# ESP-32_Stepper_Hat_v6.net
KiCad netlist of a schematic drawn in EAGLE
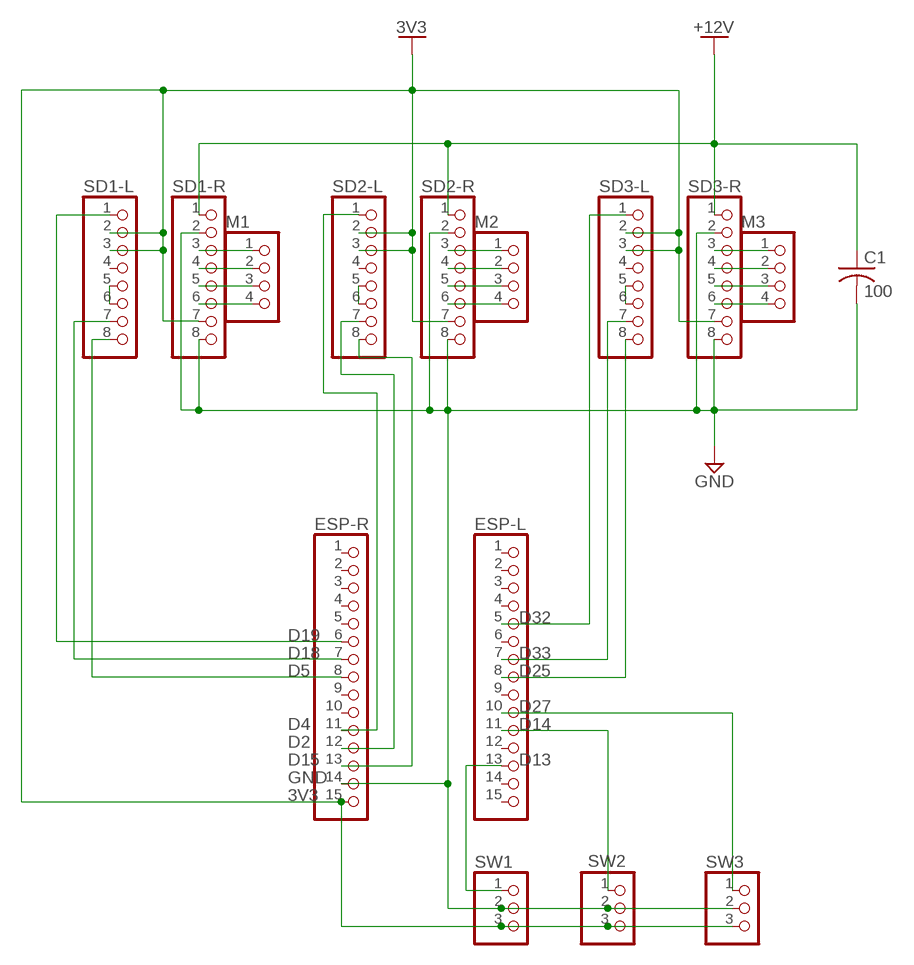
[diagram p0: schematic, sheet 1]

(export (version "E")
  (design (tool "Eeschema 10.0.6"))
  (components
    (comp (ref "C1")
      (value "100")
      (footprint "eagle-import:CAPRD550W60D1025H1250B")
      (libsource (lib "eagle-import") (part "C-USRADIAL-12.5MM-DIA_"))
    )
    (comp (ref "ESP-L")
      (value "PINHD-1X15")
      (footprint "eagle-import:1X15")
      (libsource (lib "eagle-import") (part "PINHD-1X15"))
    )
    (comp (ref "ESP-R")
      (value "PINHD-1X15")
      (footprint "eagle-import:1X15")
      (libsource (lib "eagle-import") (part "PINHD-1X15"))
    )
    (comp (ref "M1")
      (value "PINHD-1X4")
      (footprint "eagle-import:1X04")
      (libsource (lib "eagle-import") (part "PINHD-1X4"))
    )
    (comp (ref "M2")
      (value "PINHD-1X4")
      (footprint "eagle-import:1X04")
      (libsource (lib "eagle-import") (part "PINHD-1X4"))
    )
    (comp (ref "M3")
      (value "PINHD-1X4")
      (footprint "eagle-import:1X04")
      (libsource (lib "eagle-import") (part "PINHD-1X4"))
    )
    (comp (ref "SD1-L")
      (value "PINHD-1X8")
      (footprint "eagle-import:1X08")
      (libsource (lib "eagle-import") (part "PINHD-1X8"))
    )
    (comp (ref "SD1-R")
      (value "PINHD-1X8")
      (footprint "eagle-import:1X08")
      (libsource (lib "eagle-import") (part "PINHD-1X8"))
    )
    (comp (ref "SD2-L")
      (value "PINHD-1X8")
      (footprint "eagle-import:1X08")
      (libsource (lib "eagle-import") (part "PINHD-1X8"))
    )
    (comp (ref "SD2-R")
      (value "PINHD-1X8")
      (footprint "eagle-import:1X08")
      (libsource (lib "eagle-import") (part "PINHD-1X8"))
    )
    (comp (ref "SD3-L")
      (value "PINHD-1X8")
      (footprint "eagle-import:1X08")
      (libsource (lib "eagle-import") (part "PINHD-1X8"))
    )
    (comp (ref "SD3-R")
      (value "PINHD-1X8")
      (footprint "eagle-import:1X08")
      (libsource (lib "eagle-import") (part "PINHD-1X8"))
    )
    (comp (ref "SW1")
      (value "PINHD-1X3")
      (footprint "eagle-import:1X03")
      (libsource (lib "eagle-import") (part "PINHD-1X3"))
    )
    (comp (ref "SW2")
      (value "PINHD-1X3")
      (footprint "eagle-import:1X03")
      (libsource (lib "eagle-import") (part "PINHD-1X3"))
    )
    (comp (ref "SW3")
      (value "PINHD-1X3")
      (footprint "eagle-import:1X03")
      (libsource (lib "eagle-import") (part "PINHD-1X3"))
    )
  )
  (nets
    (net (code "1") (name "+12V") (class "Default")
      (node (ref "C1") (pin "1") (pinfunction "1_1") (pintype "passive"))
      (node (ref "SD1-R") (pin "1") (pinfunction "1_1") (pintype "passive"))
      (node (ref "SD2-R") (pin "1") (pinfunction "1_1") (pintype "passive"))
      (node (ref "SD3-R") (pin "1") (pinfunction "1_1") (pintype "passive"))
    )
    (net (code "2") (name "/D2") (class "Default")
      (node (ref "ESP-R") (pin "12") (pinfunction "12_12") (pintype "passive"))
      (node (ref "SD2-L") (pin "7") (pinfunction "7_7") (pintype "passive"))
    )
    (net (code "3") (name "/D4") (class "Default")
      (node (ref "ESP-R") (pin "11") (pinfunction "11_11") (pintype "passive"))
      (node (ref "SD2-L") (pin "1") (pinfunction "1_1") (pintype "passive"))
    )
    (net (code "4") (name "/D5") (class "Default")
      (node (ref "ESP-R") (pin "8") (pinfunction "8_8") (pintype "passive"))
      (node (ref "SD1-L") (pin "8") (pinfunction "8_8") (pintype "passive"))
    )
    (net (code "5") (name "/D13") (class "Default")
      (node (ref "ESP-L") (pin "13") (pinfunction "13_13") (pintype "passive"))
      (node (ref "SW1") (pin "1") (pinfunction "1_1") (pintype "passive"))
    )
    (net (code "6") (name "/D14") (class "Default")
      (node (ref "ESP-L") (pin "11") (pinfunction "11_11") (pintype "passive"))
      (node (ref "SW2") (pin "1") (pinfunction "1_1") (pintype "passive"))
    )
    (net (code "7") (name "/D15") (class "Default")
      (node (ref "ESP-R") (pin "13") (pinfunction "13_13") (pintype "passive"))
      (node (ref "SD2-L") (pin "8") (pinfunction "8_8") (pintype "passive"))
    )
    (net (code "8") (name "/D18") (class "Default")
      (node (ref "ESP-R") (pin "7") (pinfunction "7_7") (pintype "passive"))
      (node (ref "SD1-L") (pin "7") (pinfunction "7_7") (pintype "passive"))
    )
    (net (code "9") (name "/D19") (class "Default")
      (node (ref "ESP-R") (pin "6") (pinfunction "6_6") (pintype "passive"))
      (node (ref "SD1-L") (pin "1") (pinfunction "1_1") (pintype "passive"))
    )
    (net (code "10") (name "/D25") (class "Default")
      (node (ref "ESP-L") (pin "8") (pinfunction "8_8") (pintype "passive"))
      (node (ref "SD3-L") (pin "8") (pinfunction "8_8") (pintype "passive"))
    )
    (net (code "11") (name "/D27") (class "Default")
      (node (ref "ESP-L") (pin "10") (pinfunction "10_10") (pintype "passive"))
      (node (ref "SW3") (pin "1") (pinfunction "1_1") (pintype "passive"))
    )
    (net (code "12") (name "/D32") (class "Default")
      (node (ref "ESP-L") (pin "5") (pinfunction "5_5") (pintype "passive"))
      (node (ref "SD3-L") (pin "1") (pinfunction "1_1") (pintype "passive"))
    )
    (net (code "13") (name "/D33") (class "Default")
      (node (ref "ESP-L") (pin "7") (pinfunction "7_7") (pintype "passive"))
      (node (ref "SD3-L") (pin "7") (pinfunction "7_7") (pintype "passive"))
    )
    (net (code "14") (name "3V3") (class "Default")
      (node (ref "ESP-R") (pin "15") (pinfunction "15_15") (pintype "passive"))
      (node (ref "SD1-L") (pin "2") (pinfunction "2_2") (pintype "passive"))
      (node (ref "SD1-L") (pin "3") (pinfunction "3_3") (pintype "passive"))
      (node (ref "SD1-R") (pin "7") (pinfunction "7_7") (pintype "passive"))
      (node (ref "SD2-L") (pin "2") (pinfunction "2_2") (pintype "passive"))
      (node (ref "SD2-L") (pin "3") (pinfunction "3_3") (pintype "passive"))
      (node (ref "SD2-R") (pin "7") (pinfunction "7_7") (pintype "passive"))
      (node (ref "SD3-L") (pin "2") (pinfunction "2_2") (pintype "passive"))
      (node (ref "SD3-L") (pin "3") (pinfunction "3_3") (pintype "passive"))
      (node (ref "SD3-R") (pin "7") (pinfunction "7_7") (pintype "passive"))
      (node (ref "SW1") (pin "3") (pinfunction "3_3") (pintype "passive"))
      (node (ref "SW2") (pin "3") (pinfunction "3_3") (pintype "passive"))
      (node (ref "SW3") (pin "3") (pinfunction "3_3") (pintype "passive"))
    )
    (net (code "15") (name "GND") (class "Default")
      (node (ref "C1") (pin "2") (pinfunction "2_2") (pintype "passive"))
      (node (ref "ESP-R") (pin "14") (pinfunction "14_14") (pintype "passive"))
      (node (ref "SD1-R") (pin "2") (pinfunction "2_2") (pintype "passive"))
      (node (ref "SD1-R") (pin "8") (pinfunction "8_8") (pintype "passive"))
      (node (ref "SD2-R") (pin "2") (pinfunction "2_2") (pintype "passive"))
      (node (ref "SD2-R") (pin "8") (pinfunction "8_8") (pintype "passive"))
      (node (ref "SD3-R") (pin "2") (pinfunction "2_2") (pintype "passive"))
      (node (ref "SD3-R") (pin "8") (pinfunction "8_8") (pintype "passive"))
      (node (ref "SW1") (pin "2") (pinfunction "2_2") (pintype "passive"))
      (node (ref "SW2") (pin "2") (pinfunction "2_2") (pintype "passive"))
      (node (ref "SW3") (pin "2") (pinfunction "2_2") (pintype "passive"))
    )
    (net (code "16") (name "Net-(M1-Pad1)") (class "Default")
      (node (ref "M1") (pin "1") (pinfunction "1_1") (pintype "passive"))
      (node (ref "SD1-R") (pin "3") (pinfunction "3_3") (pintype "passive"))
    )
    (net (code "17") (name "Net-(M1-Pad2)") (class "Default")
      (node (ref "M1") (pin "2") (pinfunction "2_2") (pintype "passive"))
      (node (ref "SD1-R") (pin "4") (pinfunction "4_4") (pintype "passive"))
    )
    (net (code "18") (name "Net-(M1-Pad3)") (class "Default")
      (node (ref "M1") (pin "3") (pinfunction "3_3") (pintype "passive"))
      (node (ref "SD1-R") (pin "5") (pinfunction "5_5") (pintype "passive"))
    )
    (net (code "19") (name "Net-(M1-Pad4)") (class "Default")
      (node (ref "M1") (pin "4") (pinfunction "4_4") (pintype "passive"))
      (node (ref "SD1-R") (pin "6") (pinfunction "6_6") (pintype "passive"))
    )
    (net (code "20") (name "Net-(M2-Pad1)") (class "Default")
      (node (ref "M2") (pin "1") (pinfunction "1_1") (pintype "passive"))
      (node (ref "SD2-R") (pin "3") (pinfunction "3_3") (pintype "passive"))
    )
    (net (code "21") (name "Net-(M2-Pad2)") (class "Default")
      (node (ref "M2") (pin "2") (pinfunction "2_2") (pintype "passive"))
      (node (ref "SD2-R") (pin "4") (pinfunction "4_4") (pintype "passive"))
    )
    (net (code "22") (name "Net-(M2-Pad3)") (class "Default")
      (node (ref "M2") (pin "3") (pinfunction "3_3") (pintype "passive"))
      (node (ref "SD2-R") (pin "5") (pinfunction "5_5") (pintype "passive"))
    )
    (net (code "23") (name "Net-(M2-Pad4)") (class "Default")
      (node (ref "M2") (pin "4") (pinfunction "4_4") (pintype "passive"))
      (node (ref "SD2-R") (pin "6") (pinfunction "6_6") (pintype "passive"))
    )
    (net (code "24") (name "Net-(M3-Pad1)") (class "Default")
      (node (ref "M3") (pin "1") (pinfunction "1_1") (pintype "passive"))
      (node (ref "SD3-R") (pin "3") (pinfunction "3_3") (pintype "passive"))
    )
    (net (code "25") (name "Net-(M3-Pad2)") (class "Default")
      (node (ref "M3") (pin "2") (pinfunction "2_2") (pintype "passive"))
      (node (ref "SD3-R") (pin "4") (pinfunction "4_4") (pintype "passive"))
    )
    (net (code "26") (name "Net-(M3-Pad3)") (class "Default")
      (node (ref "M3") (pin "3") (pinfunction "3_3") (pintype "passive"))
      (node (ref "SD3-R") (pin "5") (pinfunction "5_5") (pintype "passive"))
    )
    (net (code "27") (name "Net-(M3-Pad4)") (class "Default")
      (node (ref "M3") (pin "4") (pinfunction "4_4") (pintype "passive"))
      (node (ref "SD3-R") (pin "6") (pinfunction "6_6") (pintype "passive"))
    )
    (net (code "28") (name "Net-(SD1-L-Pad5)") (class "Default")
      (node (ref "SD1-L") (pin "5") (pinfunction "5_5") (pintype "passive"))
      (node (ref "SD1-L") (pin "6") (pinfunction "6_6") (pintype "passive"))
    )
    (net (code "29") (name "Net-(SD2-L-Pad5)") (class "Default")
      (node (ref "SD2-L") (pin "5") (pinfunction "5_5") (pintype "passive"))
      (node (ref "SD2-L") (pin "6") (pinfunction "6_6") (pintype "passive"))
    )
    (net (code "30") (name "Net-(SD3-L-Pad5)") (class "Default")
      (node (ref "SD3-L") (pin "5") (pinfunction "5_5") (pintype "passive"))
      (node (ref "SD3-L") (pin "6") (pinfunction "6_6") (pintype "passive"))
    )
    (net (code "31") (name "unconnected-(ESP-L-Pad1)") (class "Default")
      (node (ref "ESP-L") (pin "1") (pinfunction "1_1") (pintype "passive"))
    )
    (net (code "32") (name "unconnected-(ESP-L-Pad2)") (class "Default")
      (node (ref "ESP-L") (pin "2") (pinfunction "2_2") (pintype "passive"))
    )
    (net (code "33") (name "unconnected-(ESP-L-Pad3)") (class "Default")
      (node (ref "ESP-L") (pin "3") (pinfunction "3_3") (pintype "passive"))
    )
    (net (code "34") (name "unconnected-(ESP-L-Pad4)") (class "Default")
      (node (ref "ESP-L") (pin "4") (pinfunction "4_4") (pintype "passive"))
    )
    (net (code "35") (name "unconnected-(ESP-L-Pad6)") (class "Default")
      (node (ref "ESP-L") (pin "6") (pinfunction "6_6") (pintype "passive"))
    )
    (net (code "36") (name "unconnected-(ESP-L-Pad9)") (class "Default")
      (node (ref "ESP-L") (pin "9") (pinfunction "9_9") (pintype "passive"))
    )
    (net (code "37") (name "unconnected-(ESP-L-Pad12)") (class "Default")
      (node (ref "ESP-L") (pin "12") (pinfunction "12_12") (pintype "passive"))
    )
    (net (code "38") (name "unconnected-(ESP-L-Pad14)") (class "Default")
      (node (ref "ESP-L") (pin "14") (pinfunction "14_14") (pintype "passive"))
    )
    (net (code "39") (name "unconnected-(ESP-L-Pad15)") (class "Default")
      (node (ref "ESP-L") (pin "15") (pinfunction "15_15") (pintype "passive"))
    )
    (net (code "40") (name "unconnected-(ESP-R-Pad1)") (class "Default")
      (node (ref "ESP-R") (pin "1") (pinfunction "1_1") (pintype "passive"))
    )
    (net (code "41") (name "unconnected-(ESP-R-Pad2)") (class "Default")
      (node (ref "ESP-R") (pin "2") (pinfunction "2_2") (pintype "passive"))
    )
    (net (code "42") (name "unconnected-(ESP-R-Pad3)") (class "Default")
      (node (ref "ESP-R") (pin "3") (pinfunction "3_3") (pintype "passive"))
    )
    (net (code "43") (name "unconnected-(ESP-R-Pad4)") (class "Default")
      (node (ref "ESP-R") (pin "4") (pinfunction "4_4") (pintype "passive"))
    )
    (net (code "44") (name "unconnected-(ESP-R-Pad5)") (class "Default")
      (node (ref "ESP-R") (pin "5") (pinfunction "5_5") (pintype "passive"))
    )
    (net (code "45") (name "unconnected-(ESP-R-Pad9)") (class "Default")
      (node (ref "ESP-R") (pin "9") (pinfunction "9_9") (pintype "passive"))
    )
    (net (code "46") (name "unconnected-(ESP-R-Pad10)") (class "Default")
      (node (ref "ESP-R") (pin "10") (pinfunction "10_10") (pintype "passive"))
    )
    (net (code "47") (name "unconnected-(SD1-L-Pad4)") (class "Default")
      (node (ref "SD1-L") (pin "4") (pinfunction "4_4") (pintype "passive"))
    )
    (net (code "48") (name "unconnected-(SD2-L-Pad4)") (class "Default")
      (node (ref "SD2-L") (pin "4") (pinfunction "4_4") (pintype "passive"))
    )
    (net (code "49") (name "unconnected-(SD3-L-Pad4)") (class "Default")
      (node (ref "SD3-L") (pin "4") (pinfunction "4_4") (pintype "passive"))
    )
  )
)
